# Mainboard_MCU_Breakout.net
KiCad netlist of a schematic drawn in Altium Designer
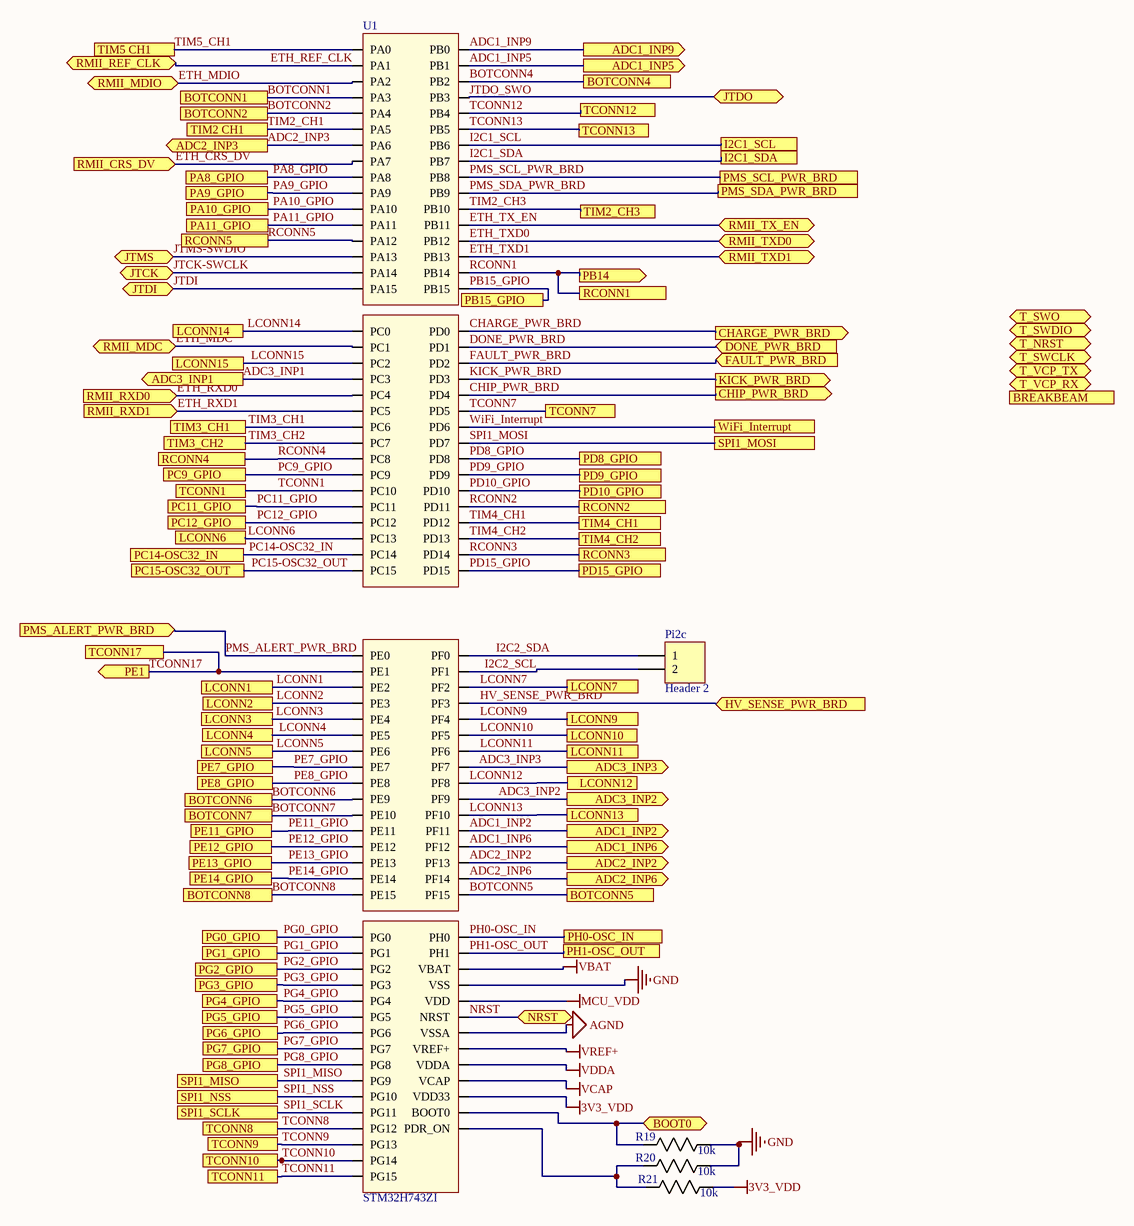
[diagram p0: Mainboard_MCU_Breakout.SchDoc]

(export (version "E")
  (design (tool "Eeschema 10.0.6"))
  (components
    (comp (ref "Pi2c")
      (value "Header 2")
      (footprint "HDR1X2")
      (description "Header, 2-Pin")
      (fields (field (name "PUBLISHER") "Altium Limited"))
      (libsource (lib "Miscellaneous Connectors") (part "Header 2"))
    )
    (comp (ref "R19")
      (value "10k")
      (footprint "0805")
      (description "RES SMD 10K OHM 1% 1/8W 0805")
      (fields (field (name "TOLERANCE") "1%"))
      (libsource (lib "AltiumLibraries") (part "RES 10k 1/8W - 1%"))
    )
    (comp (ref "R20")
      (value "10k")
      (footprint "0805")
      (description "RES SMD 10K OHM 1% 1/8W 0805")
      (fields (field (name "TOLERANCE") "1%"))
      (libsource (lib "AltiumLibraries") (part "RES 10k 1/8W - 1%"))
    )
    (comp (ref "R21")
      (value "10k")
      (footprint "0805")
      (description "RES SMD 10K OHM 1% 1/8W 0805")
      (fields (field (name "TOLERANCE") "1%"))
      (libsource (lib "AltiumLibraries") (part "RES 10k 1/8W - 1%"))
    )
    (comp (ref "U1")
      (value "STM32H743ZI")
      (footprint "STM32H7")
      (fields (field (name "MF") "STMicroelectronics") (field (name "MP") "STM32H743ZIT6"))
      (libsource (lib "AltiumLibraries") (part "STM32H743ZI"))
    )
  )
  (nets
    (net (code "1") (name "/ADC1_INP2") (class "Default")
      (node (ref "U1") (pin "PF11") (pinfunction "PF11_PF11") (pintype "passive"))
    )
    (net (code "2") (name "/ADC1_INP5") (class "Default")
      (node (ref "U1") (pin "PB1") (pinfunction "PB1_PB1") (pintype "passive"))
    )
    (net (code "3") (name "/ADC1_INP6") (class "Default")
      (node (ref "U1") (pin "PF12") (pinfunction "PF12_PF12") (pintype "passive"))
    )
    (net (code "4") (name "/ADC1_INP9") (class "Default")
      (node (ref "U1") (pin "PB0") (pinfunction "PB0_PB0") (pintype "passive"))
    )
    (net (code "5") (name "/ADC2_INP2") (class "Default")
      (node (ref "U1") (pin "PF13") (pinfunction "PF13_PF13") (pintype "passive"))
    )
    (net (code "6") (name "/ADC2_INP3") (class "Default")
      (node (ref "U1") (pin "PA6") (pinfunction "PA6_PA6") (pintype "passive"))
    )
    (net (code "7") (name "/ADC2_INP6") (class "Default")
      (node (ref "U1") (pin "PF14") (pinfunction "PF14_PF14") (pintype "passive"))
    )
    (net (code "8") (name "/ADC3_INP1") (class "Default")
      (node (ref "U1") (pin "PC3") (pinfunction "PC3_PC3") (pintype "passive"))
    )
    (net (code "9") (name "/ADC3_INP2") (class "Default")
      (node (ref "U1") (pin "PF9") (pinfunction "PF9_PF9") (pintype "passive"))
    )
    (net (code "10") (name "/ADC3_INP3") (class "Default")
      (node (ref "U1") (pin "PF7") (pinfunction "PF7_PF7") (pintype "passive"))
    )
    (net (code "11") (name "/BOOT0") (class "Default")
      (node (ref "R19") (pin "2") (pinfunction "R2_2") (pintype "passive"))
      (node (ref "U1") (pin "BOOT0") (pinfunction "BOOT0_BOOT0") (pintype "passive"))
    )
    (net (code "12") (name "/BOTCONN1") (class "Default")
      (node (ref "U1") (pin "PA3") (pinfunction "PA3_PA3") (pintype "passive"))
    )
    (net (code "13") (name "/BOTCONN2") (class "Default")
      (node (ref "U1") (pin "PA4") (pinfunction "PA4_PA4") (pintype "passive"))
    )
    (net (code "14") (name "/BOTCONN4") (class "Default")
      (node (ref "U1") (pin "PB2") (pinfunction "PB2_PB2") (pintype "passive"))
    )
    (net (code "15") (name "/BOTCONN5") (class "Default")
      (node (ref "U1") (pin "PF15") (pinfunction "PF15_PF15") (pintype "passive"))
    )
    (net (code "16") (name "/BOTCONN6") (class "Default")
      (node (ref "U1") (pin "PE9") (pinfunction "PE9_PE9") (pintype "passive"))
    )
    (net (code "17") (name "/BOTCONN7") (class "Default")
      (node (ref "U1") (pin "PE10") (pinfunction "PE10_PE10") (pintype "passive"))
    )
    (net (code "18") (name "/BOTCONN8") (class "Default")
      (node (ref "U1") (pin "PE15") (pinfunction "PE15_PE15") (pintype "passive"))
    )
    (net (code "20") (name "/CHARGE_PWR_BRD") (class "Default")
      (node (ref "U1") (pin "PD0") (pinfunction "PD0_PD0") (pintype "passive"))
    )
    (net (code "21") (name "/CHIP_PWR_BRD") (class "Default")
      (node (ref "U1") (pin "PD4") (pinfunction "PD4_PD4") (pintype "passive"))
    )
    (net (code "22") (name "/DONE_PWR_BRD") (class "Default")
      (node (ref "U1") (pin "PD1") (pinfunction "PD1_PD1") (pintype "passive"))
    )
    (net (code "23") (name "/ETH_CRS_DV") (class "Default")
      (node (ref "U1") (pin "PA7") (pinfunction "PA7_PA7") (pintype "passive"))
    )
    (net (code "24") (name "/ETH_MDC") (class "Default")
      (node (ref "U1") (pin "PC1") (pinfunction "PC1_PC1") (pintype "passive"))
    )
    (net (code "25") (name "/ETH_MDIO") (class "Default")
      (node (ref "U1") (pin "PA2") (pinfunction "PA2_PA2") (pintype "passive"))
    )
    (net (code "26") (name "/ETH_REF_CLK") (class "Default")
      (node (ref "U1") (pin "PA1") (pinfunction "PA1_PA1") (pintype "passive"))
    )
    (net (code "27") (name "/ETH_RXD0") (class "Default")
      (node (ref "U1") (pin "PC4") (pinfunction "PC4_PC4") (pintype "passive"))
    )
    (net (code "28") (name "/ETH_RXD1") (class "Default")
      (node (ref "U1") (pin "PC5") (pinfunction "PC5_PC5") (pintype "passive"))
    )
    (net (code "29") (name "/ETH_TXD0") (class "Default")
      (node (ref "U1") (pin "PB12") (pinfunction "PB12_PB12") (pintype "passive"))
    )
    (net (code "30") (name "/ETH_TXD1") (class "Default")
      (node (ref "U1") (pin "PB13") (pinfunction "PB13_PB13") (pintype "passive"))
    )
    (net (code "31") (name "/ETH_TX_EN") (class "Default")
      (node (ref "U1") (pin "PB11") (pinfunction "PB11_PB11") (pintype "passive"))
    )
    (net (code "32") (name "/FAULT_PWR_BRD") (class "Default")
      (node (ref "U1") (pin "PD2") (pinfunction "PD2_PD2") (pintype "passive"))
    )
    (net (code "33") (name "/HV_SENSE_PWR_BRD") (class "Default")
      (node (ref "U1") (pin "PF3") (pinfunction "PF3_PF3") (pintype "passive"))
    )
    (net (code "34") (name "/I2C1_SCL") (class "Default")
      (node (ref "U1") (pin "PB6") (pinfunction "PB6_PB6") (pintype "passive"))
    )
    (net (code "35") (name "/I2C1_SDA") (class "Default")
      (node (ref "U1") (pin "PB7") (pinfunction "PB7_PB7") (pintype "passive"))
    )
    (net (code "36") (name "/I2C2_SCL") (class "Default")
      (node (ref "Pi2c") (pin "2") (pinfunction "2_2") (pintype "passive"))
      (node (ref "U1") (pin "PF1") (pinfunction "PF1_PF1") (pintype "passive"))
    )
    (net (code "37") (name "/I2C2_SDA") (class "Default")
      (node (ref "Pi2c") (pin "1") (pinfunction "1_1") (pintype "passive"))
      (node (ref "U1") (pin "PF0") (pinfunction "PF0_PF0") (pintype "passive"))
    )
    (net (code "38") (name "/JTCK-SWCLK") (class "Default")
      (node (ref "U1") (pin "PA14") (pinfunction "PA14_PA14") (pintype "passive"))
    )
    (net (code "39") (name "/JTDI") (class "Default")
      (node (ref "U1") (pin "PA15") (pinfunction "PA15_PA15") (pintype "passive"))
    )
    (net (code "40") (name "/JTDO_SWO") (class "Default")
      (node (ref "U1") (pin "PB3") (pinfunction "PB3_PB3") (pintype "passive"))
    )
    (net (code "41") (name "/JTMS-SWDIO") (class "Default")
      (node (ref "U1") (pin "PA13") (pinfunction "PA13_PA13") (pintype "passive"))
    )
    (net (code "42") (name "/KICK_PWR_BRD") (class "Default")
      (node (ref "U1") (pin "PD3") (pinfunction "PD3_PD3") (pintype "passive"))
    )
    (net (code "43") (name "/LCONN1") (class "Default")
      (node (ref "U1") (pin "PE2") (pinfunction "PE2_PE2") (pintype "passive"))
    )
    (net (code "44") (name "/LCONN2") (class "Default")
      (node (ref "U1") (pin "PE3") (pinfunction "PE3_PE3") (pintype "passive"))
    )
    (net (code "45") (name "/LCONN3") (class "Default")
      (node (ref "U1") (pin "PE4") (pinfunction "PE4_PE4") (pintype "passive"))
    )
    (net (code "46") (name "/LCONN4") (class "Default")
      (node (ref "U1") (pin "PE5") (pinfunction "PE5_PE5") (pintype "passive"))
    )
    (net (code "47") (name "/LCONN5") (class "Default")
      (node (ref "U1") (pin "PE6") (pinfunction "PE6_PE6") (pintype "passive"))
    )
    (net (code "48") (name "/LCONN6") (class "Default")
      (node (ref "U1") (pin "PC13") (pinfunction "PC13_PC13") (pintype "passive"))
    )
    (net (code "49") (name "/LCONN7") (class "Default")
      (node (ref "U1") (pin "PF2") (pinfunction "PF2_PF2") (pintype "passive"))
    )
    (net (code "50") (name "/LCONN9") (class "Default")
      (node (ref "U1") (pin "PF4") (pinfunction "PF4_PF4") (pintype "passive"))
    )
    (net (code "51") (name "/LCONN10") (class "Default")
      (node (ref "U1") (pin "PF5") (pinfunction "PF5_PF5") (pintype "passive"))
    )
    (net (code "52") (name "/LCONN11") (class "Default")
      (node (ref "U1") (pin "PF6") (pinfunction "PF6_PF6") (pintype "passive"))
    )
    (net (code "53") (name "/LCONN12") (class "Default")
      (node (ref "U1") (pin "PF8") (pinfunction "PF8_PF8") (pintype "passive"))
    )
    (net (code "54") (name "/LCONN13") (class "Default")
      (node (ref "U1") (pin "PF10") (pinfunction "PF10_PF10") (pintype "passive"))
    )
    (net (code "55") (name "/LCONN14") (class "Default")
      (node (ref "U1") (pin "PC0") (pinfunction "PC0_PC0") (pintype "passive"))
    )
    (net (code "56") (name "/LCONN15") (class "Default")
      (node (ref "U1") (pin "PC2") (pinfunction "PC2_PC2") (pintype "passive"))
    )
    (net (code "57") (name "/NRST") (class "Default")
      (node (ref "U1") (pin "NRST") (pinfunction "NRST_NRST") (pintype "passive"))
    )
    (net (code "58") (name "/PA8_GPIO") (class "Default")
      (node (ref "U1") (pin "PA8") (pinfunction "PA8_PA8") (pintype "passive"))
    )
    (net (code "59") (name "/PA9_GPIO") (class "Default")
      (node (ref "U1") (pin "PA9") (pinfunction "PA9_PA9") (pintype "passive"))
    )
    (net (code "60") (name "/PA10_GPIO") (class "Default")
      (node (ref "U1") (pin "PA10") (pinfunction "PA10_PA10") (pintype "passive"))
    )
    (net (code "61") (name "/PA11_GPIO") (class "Default")
      (node (ref "U1") (pin "PA11") (pinfunction "PA11_PA11") (pintype "passive"))
    )
    (net (code "62") (name "/PB15_GPIO") (class "Default")
      (node (ref "U1") (pin "PB15") (pinfunction "PB15_PB15") (pintype "passive"))
    )
    (net (code "63") (name "/PC9_GPIO") (class "Default")
      (node (ref "U1") (pin "PC9") (pinfunction "PC9_PC9") (pintype "passive"))
    )
    (net (code "64") (name "/PC11_GPIO") (class "Default")
      (node (ref "U1") (pin "PC11") (pinfunction "PC11_PC11") (pintype "passive"))
    )
    (net (code "65") (name "/PC12_GPIO") (class "Default")
      (node (ref "U1") (pin "PC12") (pinfunction "PC12_PC12") (pintype "passive"))
    )
    (net (code "66") (name "/PC14-OSC32_IN") (class "Default")
      (node (ref "U1") (pin "PC14") (pinfunction "PC14_PC14") (pintype "passive"))
    )
    (net (code "67") (name "/PC15-OSC32_OUT") (class "Default")
      (node (ref "U1") (pin "PC15") (pinfunction "PC15_PC15") (pintype "passive"))
    )
    (net (code "68") (name "/PD8_GPIO") (class "Default")
      (node (ref "U1") (pin "PD8") (pinfunction "PD8_PD8") (pintype "passive"))
    )
    (net (code "69") (name "/PD9_GPIO") (class "Default")
      (node (ref "U1") (pin "PD9") (pinfunction "PD9_PD9") (pintype "passive"))
    )
    (net (code "70") (name "/PD10_GPIO") (class "Default")
      (node (ref "U1") (pin "PD10") (pinfunction "PD10_PD10") (pintype "passive"))
    )
    (net (code "71") (name "/PD15_GPIO") (class "Default")
      (node (ref "U1") (pin "PD15") (pinfunction "PD15_PD15") (pintype "passive"))
    )
    (net (code "72") (name "/PE7_GPIO") (class "Default")
      (node (ref "U1") (pin "PE7") (pinfunction "PE7_PE7") (pintype "passive"))
    )
    (net (code "73") (name "/PE8_GPIO") (class "Default")
      (node (ref "U1") (pin "PE8") (pinfunction "PE8_PE8") (pintype "passive"))
    )
    (net (code "74") (name "/PE11_GPIO") (class "Default")
      (node (ref "U1") (pin "PE11") (pinfunction "PE11_PE11") (pintype "passive"))
    )
    (net (code "75") (name "/PE12_GPIO") (class "Default")
      (node (ref "U1") (pin "PE12") (pinfunction "PE12_PE12") (pintype "passive"))
    )
    (net (code "76") (name "/PE13_GPIO") (class "Default")
      (node (ref "U1") (pin "PE13") (pinfunction "PE13_PE13") (pintype "passive"))
    )
    (net (code "77") (name "/PE14_GPIO") (class "Default")
      (node (ref "U1") (pin "PE14") (pinfunction "PE14_PE14") (pintype "passive"))
    )
    (net (code "78") (name "/PG0_GPIO") (class "Default")
      (node (ref "U1") (pin "PG0") (pinfunction "PG0_PG0") (pintype "passive"))
    )
    (net (code "79") (name "/PG1_GPIO") (class "Default")
      (node (ref "U1") (pin "PG1") (pinfunction "PG1_PG1") (pintype "passive"))
    )
    (net (code "80") (name "/PG2_GPIO") (class "Default")
      (node (ref "U1") (pin "PG2") (pinfunction "PG2_PG2") (pintype "passive"))
    )
    (net (code "81") (name "/PG3_GPIO") (class "Default")
      (node (ref "U1") (pin "PG3") (pinfunction "PG3_PG3") (pintype "passive"))
    )
    (net (code "82") (name "/PG4_GPIO") (class "Default")
      (node (ref "U1") (pin "PG4") (pinfunction "PG4_PG4") (pintype "passive"))
    )
    (net (code "83") (name "/PG5_GPIO") (class "Default")
      (node (ref "U1") (pin "PG5") (pinfunction "PG5_PG5") (pintype "passive"))
    )
    (net (code "84") (name "/PG6_GPIO") (class "Default")
      (node (ref "U1") (pin "PG6") (pinfunction "PG6_PG6") (pintype "passive"))
    )
    (net (code "85") (name "/PG7_GPIO") (class "Default")
      (node (ref "U1") (pin "PG7") (pinfunction "PG7_PG7") (pintype "passive"))
    )
    (net (code "86") (name "/PG8_GPIO") (class "Default")
      (node (ref "U1") (pin "PG8") (pinfunction "PG8_PG8") (pintype "passive"))
    )
    (net (code "87") (name "/PH0-OSC_IN") (class "Default")
      (node (ref "U1") (pin "PH0") (pinfunction "PH0_PH0") (pintype "passive"))
    )
    (net (code "88") (name "/PH1-OSC_OUT") (class "Default")
      (node (ref "U1") (pin "PH1") (pinfunction "PH1_PH1") (pintype "passive"))
    )
    (net (code "89") (name "/PMS_ALERT_PWR_BRD") (class "Default")
      (node (ref "U1") (pin "PE0") (pinfunction "PE0_PE0") (pintype "passive"))
    )
    (net (code "90") (name "/PMS_SCL_PWR_BRD") (class "Default")
      (node (ref "U1") (pin "PB8") (pinfunction "PB8_PB8") (pintype "passive"))
    )
    (net (code "91") (name "/PMS_SDA_PWR_BRD") (class "Default")
      (node (ref "U1") (pin "PB9") (pinfunction "PB9_PB9") (pintype "passive"))
    )
    (net (code "92") (name "/RCONN1") (class "Default")
      (node (ref "U1") (pin "PB14") (pinfunction "PB14_PB14") (pintype "passive"))
    )
    (net (code "93") (name "/RCONN2") (class "Default")
      (node (ref "U1") (pin "PD11") (pinfunction "PD11_PD11") (pintype "passive"))
    )
    (net (code "94") (name "/RCONN3") (class "Default")
      (node (ref "U1") (pin "PD14") (pinfunction "PD14_PD14") (pintype "passive"))
    )
    (net (code "95") (name "/RCONN4") (class "Default")
      (node (ref "U1") (pin "PC8") (pinfunction "PC8_PC8") (pintype "passive"))
    )
    (net (code "96") (name "/RCONN5") (class "Default")
      (node (ref "U1") (pin "PA12") (pinfunction "PA12_PA12") (pintype "passive"))
    )
    (net (code "97") (name "/SPI1_MISO") (class "Default")
      (node (ref "U1") (pin "PG9") (pinfunction "PG9_PG9") (pintype "passive"))
    )
    (net (code "98") (name "/SPI1_MOSI") (class "Default")
      (node (ref "U1") (pin "PD7") (pinfunction "PD7_PD7") (pintype "passive"))
    )
    (net (code "99") (name "/SPI1_NSS") (class "Default")
      (node (ref "U1") (pin "PG10") (pinfunction "PG10_PG10") (pintype "passive"))
    )
    (net (code "100") (name "/SPI1_SCLK") (class "Default")
      (node (ref "U1") (pin "PG11") (pinfunction "PG11_PG11") (pintype "passive"))
    )
    (net (code "101") (name "/TCONN1") (class "Default")
      (node (ref "U1") (pin "PC10") (pinfunction "PC10_PC10") (pintype "passive"))
    )
    (net (code "102") (name "/TCONN7") (class "Default")
      (node (ref "U1") (pin "PD5") (pinfunction "PD5_PD5") (pintype "passive"))
    )
    (net (code "103") (name "/TCONN8") (class "Default")
      (node (ref "U1") (pin "PG12") (pinfunction "PG12_PG12") (pintype "passive"))
    )
    (net (code "104") (name "/TCONN9") (class "Default")
      (node (ref "U1") (pin "PG13") (pinfunction "PG13_PG13") (pintype "passive"))
    )
    (net (code "105") (name "/TCONN10") (class "Default")
      (node (ref "U1") (pin "PG14") (pinfunction "PG14_PG14") (pintype "passive"))
    )
    (net (code "106") (name "/TCONN11") (class "Default")
      (node (ref "U1") (pin "PG15") (pinfunction "PG15_PG15") (pintype "passive"))
    )
    (net (code "107") (name "/TCONN12") (class "Default")
      (node (ref "U1") (pin "PB4") (pinfunction "PB4_PB4") (pintype "passive"))
    )
    (net (code "108") (name "/TCONN13") (class "Default")
      (node (ref "U1") (pin "PB5") (pinfunction "PB5_PB5") (pintype "passive"))
    )
    (net (code "109") (name "/TCONN17") (class "Default")
      (node (ref "U1") (pin "PE1") (pinfunction "PE1_PE1") (pintype "passive"))
    )
    (net (code "110") (name "/TIM2_CH1") (class "Default")
      (node (ref "U1") (pin "PA5") (pinfunction "PA5_PA5") (pintype "passive"))
    )
    (net (code "111") (name "/TIM2_CH3") (class "Default")
      (node (ref "U1") (pin "PB10") (pinfunction "PB10_PB10") (pintype "passive"))
    )
    (net (code "112") (name "/TIM3_CH1") (class "Default")
      (node (ref "U1") (pin "PC6") (pinfunction "PC6_PC6") (pintype "passive"))
    )
    (net (code "113") (name "/TIM3_CH2") (class "Default")
      (node (ref "U1") (pin "PC7") (pinfunction "PC7_PC7") (pintype "passive"))
    )
    (net (code "114") (name "/TIM4_CH1") (class "Default")
      (node (ref "U1") (pin "PD12") (pinfunction "PD12_PD12") (pintype "passive"))
    )
    (net (code "115") (name "/TIM4_CH2") (class "Default")
      (node (ref "U1") (pin "PD13") (pinfunction "PD13_PD13") (pintype "passive"))
    )
    (net (code "116") (name "/TIM5_CH1") (class "Default")
      (node (ref "U1") (pin "PA0") (pinfunction "PA0_PA0") (pintype "passive"))
    )
    (net (code "123") (name "/WiFi_Interrupt") (class "Default")
      (node (ref "U1") (pin "PD6") (pinfunction "PD6_PD6") (pintype "passive"))
    )
    (net (code "124") (name "3V3_VDD") (class "Default")
      (node (ref "R21") (pin "1") (pinfunction "R1_1") (pintype "passive"))
      (node (ref "U1") (pin "VDD33USB") (pinfunction "VDD33_VDD33USB") (pintype "passive"))
    )
    (net (code "125") (name "AGND") (class "Default")
      (node (ref "U1") (pin "VSSA") (pinfunction "VSSA_VSSA") (pintype "passive"))
    )
    (net (code "126") (name "GND") (class "Default")
      (node (ref "R19") (pin "1") (pinfunction "R1_1") (pintype "passive"))
      (node (ref "R20") (pin "1") (pinfunction "R1_1") (pintype "passive"))
      (node (ref "U1") (pin "VSS") (pinfunction "VSS_VSS") (pintype "passive"))
    )
    (net (code "127") (name "MCU_VDD") (class "Default")
      (node (ref "U1") (pin "VDD") (pinfunction "VDD_VDD") (pintype "passive"))
    )
    (net (code "128") (name "Net-(R20-R2)") (class "Default")
      (node (ref "R20") (pin "2") (pinfunction "R2_2") (pintype "passive"))
      (node (ref "R21") (pin "2") (pinfunction "R2_2") (pintype "passive"))
      (node (ref "U1") (pin "PDR_ON") (pinfunction "PDR_ON_PDR_ON") (pintype "passive"))
    )
    (net (code "129") (name "VBAT") (class "Default")
      (node (ref "U1") (pin "VBAT") (pinfunction "VBAT_VBAT") (pintype "passive"))
    )
    (net (code "130") (name "VCAP") (class "Default")
      (node (ref "U1") (pin "VCAP") (pinfunction "VCAP_VCAP") (pintype "passive"))
    )
    (net (code "131") (name "VDDA") (class "Default")
      (node (ref "U1") (pin "VDDA") (pinfunction "VDDA_VDDA") (pintype "passive"))
    )
    (net (code "132") (name "VREF+") (class "Default")
      (node (ref "U1") (pin "VREF+") (pinfunction "VREF+_VREF+") (pintype "passive"))
    )
  )
)
